# moduloSensores.net
KiCad netlist of a schematic drawn in EAGLE
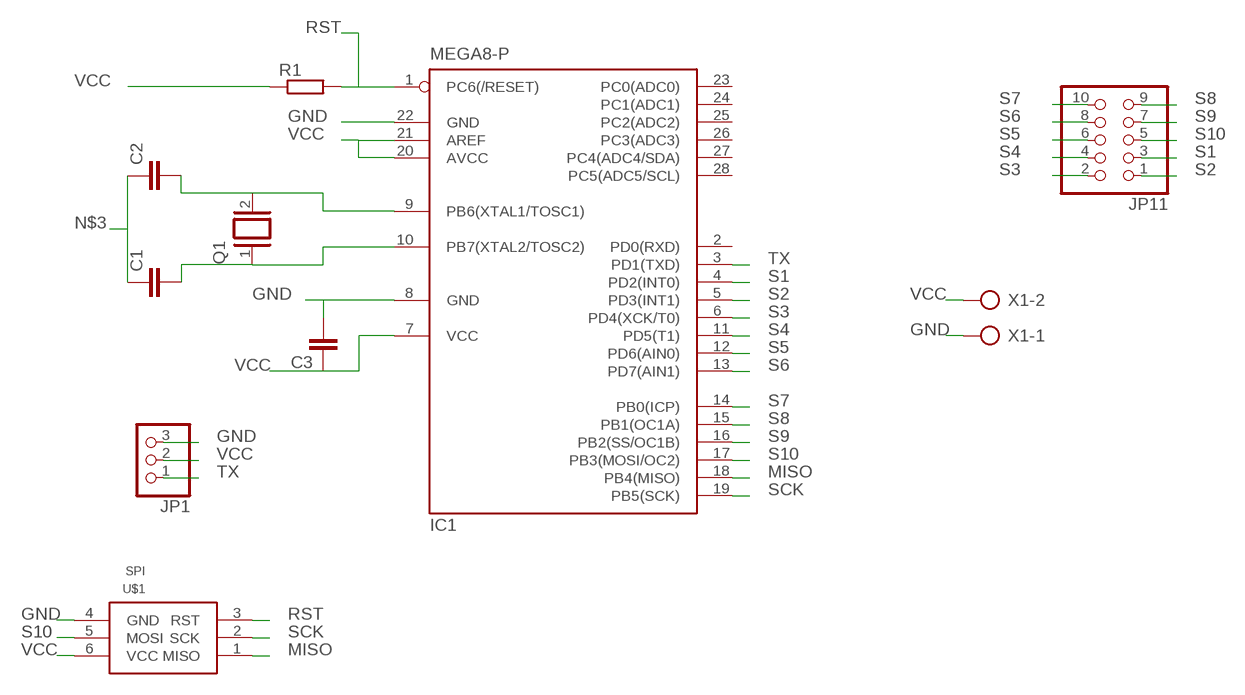
[diagram p0: schematic, sheet 1]

(export (version "E")
  (design (tool "Eeschema 10.0.6"))
  (components
    (comp (ref "C1")
      (value "C-EU050-025X075")
      (footprint "eagle-import:C050-025X075")
      (libsource (lib "eagle-import") (part "C-EU050-025X075"))
    )
    (comp (ref "C2")
      (value "C-EU050-025X075")
      (footprint "eagle-import:C050-025X075")
      (libsource (lib "eagle-import") (part "C-EU050-025X075"))
    )
    (comp (ref "C3")
      (value "C-EU050-025X075")
      (footprint "eagle-import:C050-025X075")
      (libsource (lib "eagle-import") (part "C-EU050-025X075"))
    )
    (comp (ref "IC1")
      (value "MEGA8-P")
      (footprint "eagle-import:DIL28-3")
      (libsource (lib "eagle-import") (part "MEGA8-P"))
    )
    (comp (ref "JP1")
      (value "PINHD-1X3")
      (footprint "eagle-import:1X03")
      (libsource (lib "eagle-import") (part "PINHD-1X3"))
    )
    (comp (ref "JP11")
      (value "PINHD-2X5")
      (footprint "eagle-import:2X05")
      (libsource (lib "eagle-import") (part "PINHD-2X5"))
    )
    (comp (ref "Q1")
      (value "XTAL/S")
      (footprint "eagle-import:QS")
      (libsource (lib "eagle-import") (part "XTAL/S"))
    )
    (comp (ref "R1")
      (value "R-EU_0204/7")
      (footprint "eagle-import:0204_7")
      (libsource (lib "eagle-import") (part "R-EU_0204/7"))
    )
    (comp (ref "U$1")
      (value "SPI")
      (footprint "eagle-import:HEAD-2X3")
      (libsource (lib "eagle-import") (part "SPI"))
    )
    (comp (ref "X1")
      (value "AK500/2")
      (footprint "eagle-import:AK500_2")
      (libsource (lib "eagle-import") (part "AK500/2"))
    )
  )
  (nets
    (net (code "1") (name "/GND") (class "Default")
      (node (ref "C3") (pin "2") (pinfunction "2_2") (pintype "passive"))
      (node (ref "IC1") (pin "22") (pinfunction "GND_22") (pintype "power_in"))
      (node (ref "IC1") (pin "8") (pinfunction "GND_8") (pintype "power_in"))
      (node (ref "JP1") (pin "3") (pinfunction "3_3") (pintype "passive"))
      (node (ref "U$1") (pin "4") (pinfunction "GND_4") (pintype "bidirectional"))
      (node (ref "X1") (pin "1") (pinfunction "KL_1") (pintype "passive"))
    )
    (net (code "2") (name "/MISO") (class "Default")
      (node (ref "IC1") (pin "18") (pinfunction "PB4(MISO)_18") (pintype "bidirectional"))
      (node (ref "U$1") (pin "1") (pinfunction "MISO_1") (pintype "bidirectional"))
    )
    (net (code "3") (name "/N$3") (class "Default")
      (node (ref "C1") (pin "1") (pinfunction "1_1") (pintype "passive"))
      (node (ref "C2") (pin "1") (pinfunction "1_1") (pintype "passive"))
    )
    (net (code "4") (name "/RST") (class "Default")
      (node (ref "IC1") (pin "1") (pinfunction "PC6(/RESET)_1") (pintype "bidirectional"))
      (node (ref "R1") (pin "2") (pinfunction "2_2") (pintype "passive"))
      (node (ref "U$1") (pin "3") (pinfunction "RST_3") (pintype "bidirectional"))
    )
    (net (code "5") (name "/S1") (class "Default")
      (node (ref "IC1") (pin "4") (pinfunction "PD2(INT0)_4") (pintype "bidirectional"))
      (node (ref "JP11") (pin "3") (pinfunction "3_3") (pintype "passive"))
    )
    (net (code "6") (name "/S2") (class "Default")
      (node (ref "IC1") (pin "5") (pinfunction "PD3(INT1)_5") (pintype "bidirectional"))
      (node (ref "JP11") (pin "1") (pinfunction "1_1") (pintype "passive"))
    )
    (net (code "7") (name "/S3") (class "Default")
      (node (ref "IC1") (pin "6") (pinfunction "PD4(XCK/T0)_6") (pintype "bidirectional"))
      (node (ref "JP11") (pin "2") (pinfunction "2_2") (pintype "passive"))
    )
    (net (code "8") (name "/S4") (class "Default")
      (node (ref "IC1") (pin "11") (pinfunction "PD5(T1)_11") (pintype "bidirectional"))
      (node (ref "JP11") (pin "4") (pinfunction "4_4") (pintype "passive"))
    )
    (net (code "9") (name "/S5") (class "Default")
      (node (ref "IC1") (pin "12") (pinfunction "PD6(AIN0)_12") (pintype "bidirectional"))
      (node (ref "JP11") (pin "6") (pinfunction "6_6") (pintype "passive"))
    )
    (net (code "10") (name "/S6") (class "Default")
      (node (ref "IC1") (pin "13") (pinfunction "PD7(AIN1)_13") (pintype "bidirectional"))
      (node (ref "JP11") (pin "8") (pinfunction "8_8") (pintype "passive"))
    )
    (net (code "11") (name "/S7") (class "Default")
      (node (ref "IC1") (pin "14") (pinfunction "PB0(ICP)_14") (pintype "bidirectional"))
      (node (ref "JP11") (pin "10") (pinfunction "10_10") (pintype "passive"))
    )
    (net (code "12") (name "/S8") (class "Default")
      (node (ref "IC1") (pin "15") (pinfunction "PB1(OC1A)_15") (pintype "bidirectional"))
      (node (ref "JP11") (pin "9") (pinfunction "9_9") (pintype "passive"))
    )
    (net (code "13") (name "/S9") (class "Default")
      (node (ref "IC1") (pin "16") (pinfunction "PB2(SS/OC1B)_16") (pintype "bidirectional"))
      (node (ref "JP11") (pin "7") (pinfunction "7_7") (pintype "passive"))
    )
    (net (code "14") (name "/S10") (class "Default")
      (node (ref "IC1") (pin "17") (pinfunction "PB3(MOSI/OC2)_17") (pintype "bidirectional"))
      (node (ref "JP11") (pin "5") (pinfunction "5_5") (pintype "passive"))
      (node (ref "U$1") (pin "5") (pinfunction "MOSI_5") (pintype "bidirectional"))
    )
    (net (code "15") (name "/SCK") (class "Default")
      (node (ref "IC1") (pin "19") (pinfunction "PB5(SCK)_19") (pintype "bidirectional"))
      (node (ref "U$1") (pin "2") (pinfunction "SCK_2") (pintype "bidirectional"))
    )
    (net (code "16") (name "/TX") (class "Default")
      (node (ref "IC1") (pin "3") (pinfunction "PD1(TXD)_3") (pintype "bidirectional"))
      (node (ref "JP1") (pin "1") (pinfunction "1_1") (pintype "passive"))
    )
    (net (code "17") (name "/VCC") (class "Default")
      (node (ref "C3") (pin "1") (pinfunction "1_1") (pintype "passive"))
      (node (ref "IC1") (pin "20") (pinfunction "AVCC_20") (pintype "power_in"))
      (node (ref "IC1") (pin "21") (pinfunction "AREF_21") (pintype "passive"))
      (node (ref "IC1") (pin "7") (pinfunction "VCC_7") (pintype "power_in"))
      (node (ref "JP1") (pin "2") (pinfunction "2_2") (pintype "passive"))
      (node (ref "R1") (pin "1") (pinfunction "1_1") (pintype "passive"))
      (node (ref "U$1") (pin "6") (pinfunction "VCC_6") (pintype "bidirectional"))
      (node (ref "X1") (pin "2") (pinfunction "KL_2") (pintype "passive"))
    )
    (net (code "18") (name "Net-(IC1-PB6(XTAL1{slash}TOSC1))") (class "Default")
      (node (ref "C2") (pin "2") (pinfunction "2_2") (pintype "passive"))
      (node (ref "IC1") (pin "9") (pinfunction "PB6(XTAL1/TOSC1)_9") (pintype "bidirectional"))
      (node (ref "Q1") (pin "2") (pinfunction "2_2") (pintype "passive"))
    )
    (net (code "19") (name "Net-(IC1-PB7(XTAL2{slash}TOSC2))") (class "Default")
      (node (ref "C1") (pin "2") (pinfunction "2_2") (pintype "passive"))
      (node (ref "IC1") (pin "10") (pinfunction "PB7(XTAL2/TOSC2)_10") (pintype "bidirectional"))
      (node (ref "Q1") (pin "1") (pinfunction "1_1") (pintype "passive"))
    )
    (net (code "20") (name "unconnected-(IC1-PC0(ADC0)-Pad23)") (class "Default")
      (node (ref "IC1") (pin "23") (pinfunction "PC0(ADC0)_23") (pintype "bidirectional"))
    )
    (net (code "21") (name "unconnected-(IC1-PC1(ADC1)-Pad24)") (class "Default")
      (node (ref "IC1") (pin "24") (pinfunction "PC1(ADC1)_24") (pintype "bidirectional"))
    )
    (net (code "22") (name "unconnected-(IC1-PC2(ADC2)-Pad25)") (class "Default")
      (node (ref "IC1") (pin "25") (pinfunction "PC2(ADC2)_25") (pintype "bidirectional"))
    )
    (net (code "23") (name "unconnected-(IC1-PC3(ADC3)-Pad26)") (class "Default")
      (node (ref "IC1") (pin "26") (pinfunction "PC3(ADC3)_26") (pintype "bidirectional"))
    )
    (net (code "24") (name "unconnected-(IC1-PC4(ADC4{slash}SDA)-Pad27)") (class "Default")
      (node (ref "IC1") (pin "27") (pinfunction "PC4(ADC4/SDA)_27") (pintype "bidirectional"))
    )
    (net (code "25") (name "unconnected-(IC1-PC5(ADC5{slash}SCL)-Pad28)") (class "Default")
      (node (ref "IC1") (pin "28") (pinfunction "PC5(ADC5/SCL)_28") (pintype "bidirectional"))
    )
    (net (code "26") (name "unconnected-(IC1-PD0(RXD)-Pad2)") (class "Default")
      (node (ref "IC1") (pin "2") (pinfunction "PD0(RXD)_2") (pintype "bidirectional"))
    )
  )
)
